# Power.net
KiCad netlist of a schematic drawn in Altium Designer
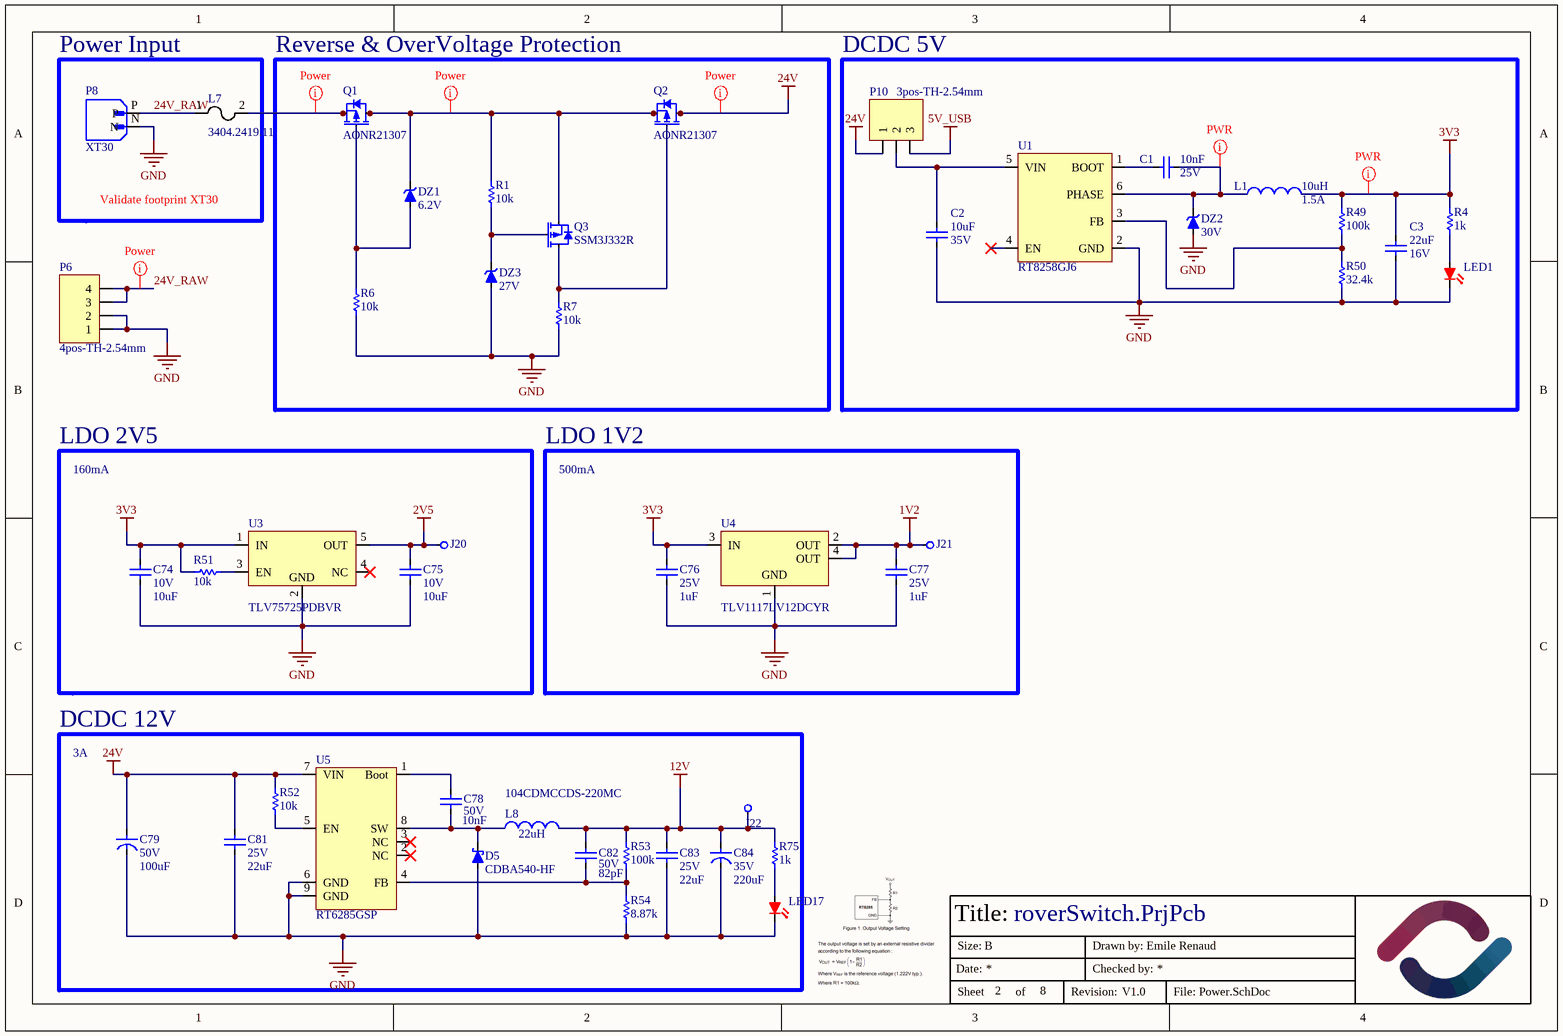
[diagram p0: Power.SchDoc]

(export (version "E")
  (design (tool "Eeschema 10.0.6"))
  (components
    (comp (ref "C1")
      (value "10nF")
      (footprint "CAPACITOR-0603")
      (description "10000 pF ±10% 25V Ceramic Capacitor X5R 0603 (1608 Metric)")
      (fields (field (name "VOLT") "25V") (field (name "Comment") "Capacitor-0603-10nF-25V-X5R"))
      (libsource (lib "Capacitors") (part "Capacitor-0603-10nF-25V-X5R"))
    )
    (comp (ref "C2")
      (value "10uF")
      (footprint "CAPACITOR-0805")
      (description "Capacitor-0805-10uF-35V-X5R")
      (fields (field (name "VOLT") "35V"))
      (libsource (lib "Capacitors") (part "Capacitor-0805-10uF-35V-X5R"))
    )
    (comp (ref "C3")
      (value "22uF")
      (footprint "CAPACITOR-0805")
      (description "Capacitor-0805-22uF-16V-X5R")
      (fields (field (name "VOLT") "16V"))
      (libsource (lib "Capacitors") (part "Capacitor-0805-22uF-16V-X5R"))
    )
    (comp (ref "C74")
      (value "10uF")
      (footprint "CAPACITOR-0603")
      (description "10 µF ±20% 10V Ceramic Capacitor X5R 0603 (1608 Metric)")
      (fields (field (name "VOLT") "10V") (field (name "Comment") "Capacitor-0603-10uF-10V-X5R"))
      (libsource (lib "Capacitors") (part "Capacitor-0603-10uF-10V-X5R"))
    )
    (comp (ref "C75")
      (value "10uF")
      (footprint "CAPACITOR-0603")
      (description "10 µF ±20% 10V Ceramic Capacitor X5R 0603 (1608 Metric)")
      (fields (field (name "VOLT") "10V") (field (name "Comment") "Capacitor-0603-10uF-10V-X5R"))
      (libsource (lib "Capacitors") (part "Capacitor-0603-10uF-10V-X5R"))
    )
    (comp (ref "C76")
      (value "1uF")
      (footprint "CAPACITOR-0603")
      (description "Capacitor-0603-1uF-25V-X5R")
      (fields (field (name "VOLT") "25V"))
      (libsource (lib "Capacitors") (part "Capacitor-0603-1uF-25V-X5R"))
    )
    (comp (ref "C77")
      (value "1uF")
      (footprint "CAPACITOR-0603")
      (description "Capacitor-0603-1uF-25V-X5R")
      (fields (field (name "VOLT") "25V"))
      (libsource (lib "Capacitors") (part "Capacitor-0603-1uF-25V-X5R"))
    )
    (comp (ref "C78")
      (value "10nF")
      (footprint "CAPACITOR-0603")
      (description "Capacitor-0603-10nF-50V-X7R")
      (fields (field (name "VOLT") "50V"))
      (libsource (lib "Capacitors") (part "Capacitor-0603-10nF-50V-X7R"))
    )
    (comp (ref "C79")
      (value "100uF")
      (footprint "CAP_J-V_8X10P5_RUB")
      (description "CAP ALUM 100UF 20% 50V SMD")
      (fields (field (name "VOLT") "50V") (field (name "Comment") "CAP ALUM 100UF 20% 25V SMD"))
      (libsource (lib "Capacitors-Electrolytic") (part "Capacitor-100uF-50V-SMD"))
    )
    (comp (ref "C81")
      (value "22uF")
      (footprint "CAPACITOR-0805")
      (description "Capacitor-0805-22uF-25V-X5R")
      (fields (field (name "VOLT") "25V"))
      (libsource (lib "Capacitors") (part "Capacitor-0805-22uF-25V-X5R"))
    )
    (comp (ref "C82")
      (value "82pF")
      (footprint "CAPACITOR-0603")
      (description "Capacitor-0603-82pF-50V-C0G")
      (fields (field (name "VOLT") "50V"))
      (libsource (lib "Capacitors") (part "Capacitor-0603-82pF-50V-C0G"))
    )
    (comp (ref "C83")
      (value "22uF")
      (footprint "CAPACITOR-0805")
      (description "Capacitor-0805-22uF-25V-X5R")
      (fields (field (name "VOLT") "25V"))
      (libsource (lib "Capacitors") (part "Capacitor-0805-22uF-25V-X5R"))
    )
    (comp (ref "C84")
      (value "220uF")
      (footprint "CAP_J-V_8X10P5_RUB")
      (description "CAP ALUM 220UF 20% 35V SMD")
      (fields (field (name "VOLT") "35V"))
      (libsource (lib "Capacitors-Electrolytic") (part "Capacitor-220uF-35V-SMD"))
    )
    (comp (ref "D5")
      (value "CDBA540-HF")
      (footprint "SMA/DO-214AC")
      (description "DIODE SCHOTTKY 40V 5A SMA")
      (libsource (lib "diodes") (part "CDBA540-HF"))
    )
    (comp (ref "DZ1")
      (value "BZT52C6V2-TP")
      (footprint "SOD-123")
      (description "Zener Diode 6.2 V 200 mW ±6% Surface Mount SOD-123")
      (fields (field (name "VOLT") "6.2V"))
      (libsource (lib "diodes-zener") (part "BZT52C6V2-TP"))
    )
    (comp (ref "DZ2")
      (value "MSS1P3L-M3/89A")
      (footprint "DO-219AD")
      (description "Diode 30 V 1A Surface Mount MicroSMP (DO-219AD)")
      (fields (field (name "VOLT") "30V"))
      (libsource (lib "diodes-zener") (part "MSS1P3L-M3/89A"))
    )
    (comp (ref "DZ3")
      (value "MMSZ5254B-TP")
      (footprint "SOD-123F")
      (description "DIODE ZENER 27V 500MW SOD123")
      (fields (field (name "VOLT") "27V"))
      (libsource (lib "diodes-zener") (part "MMSZ5254B-TP"))
    )
    (comp (ref "J20")
      (value "hole")
      (footprint "PCB_Footprints:PAD-0.53MM")
      (description "PAD for 28 AWG Solid Wire")
      (libsource (lib "JumpersAndHoles") (part "PAD 0.53mm AWG28-Solid"))
    )
    (comp (ref "J21")
      (value "hole")
      (footprint "PCB_Footprints:PAD-0.53MM")
      (description "PAD for 28 AWG Solid Wire")
      (libsource (lib "JumpersAndHoles") (part "PAD 0.53mm AWG28-Solid"))
    )
    (comp (ref "J22")
      (value "hole")
      (footprint "PCB_Footprints:PAD-0.53MM")
      (description "PAD for 28 AWG Solid Wire")
      (libsource (lib "JumpersAndHoles") (part "PAD 0.53mm AWG28-Solid"))
    )
    (comp (ref "L1")
      (value "10uH")
      (footprint "INDUCTOR_ASPI-4030S-100M")
      (description "10 µH Shielded Drum Core, Wirewound Inductor 1.5 A 100mOhm Nonstandard")
      (fields (field (name "CURRENT") "1.5A") (field (name "Comment") "ASPI-4030S-100M-T"))
      (libsource (lib "Inductors") (part "ASPI-4030S-100M-T"))
    )
    (comp (ref "L7")
      (value "3404.2419.11")
      (footprint "2-SMD-Fuse")
      (libsource (lib "Fuses") (part "3404.2419.11"))
    )
    (comp (ref "L8")
      (value "104CDMCCDS-220MC")
      (footprint "Inductor_22UH 5A")
      (description "FIXED IND 22UH 5A 66 MOHM SMD")
      (fields (field (name "ALTIUM_VALUE") "22uH"))
      (libsource (lib "Inductors") (part "104CDMCCDS-220MC"))
    )
    (comp (ref "LED1")
      (value "B1911USD-20D000114U1930")
      (footprint "LED-0603-2PIN")
      (description "LED RED CLEAR 1608 SMD")
      (libsource (lib "LEDs") (part "B1911USD-20D000114U1930"))
    )
    (comp (ref "LED17")
      (value "B1911USD-20D000114U1930")
      (footprint "LED-0603-2PIN")
      (description "LED RED CLEAR 1608 SMD")
      (libsource (lib "LEDs") (part "B1911USD-20D000114U1930"))
    )
    (comp (ref "P6")
      (value "4pos-TH-2.54mm")
      (footprint "HDR1X4")
      (description "4pos TH 2.54mm Header")
      (libsource (lib "Header") (part "4pos-TH-2.54mm"))
    )
    (comp (ref "P8")
      (value "XT30")
      (footprint "XT30PW_smd")
      (libsource (lib "BatteriesConnector") (part "XT30_pcb"))
    )
    (comp (ref "P10")
      (value "3pos-TH-2.54mm")
      (footprint "HDR1X3")
      (description "3pos TH 2.54mm Header")
      (libsource (lib "Header") (part "3pos-TH-2.54mm"))
    )
    (comp (ref "Q1")
      (value "AONR21307")
      (footprint "DFN8_3x3_Power")
      (description "MOSFET P-CH 30V 24A 8DFN")
      (libsource (lib "FET-P-Small") (part "AONR21307"))
    )
    (comp (ref "Q2")
      (value "AONR21307")
      (footprint "DFN8_3x3_Power")
      (description "MOSFET P-CH 30V 24A 8DFN")
      (libsource (lib "FET-P-Small") (part "AONR21307"))
    )
    (comp (ref "Q3")
      (value "SSM3J332R")
      (footprint "SOT-23-3")
      (description "P-Channel 30 V 6A (Ta) 1W (Ta) Surface Mount SOT-23F")
      (libsource (lib "FET-P-Small") (part "SSM3J332R"))
    )
    (comp (ref "R1")
      (value "10k")
      (footprint "Resistor-0603")
      (description "Resistor0603-10k")
      (fields (field (name "Comment") "SMT resistor"))
      (libsource (lib "Resistors") (part "Resistor0603-10k"))
    )
    (comp (ref "R4")
      (value "1k")
      (footprint "Resistor-0603")
      (description "Resistor0603-1k")
      (fields (field (name "Comment") "SMT resistor"))
      (libsource (lib "Resistors") (part "Resistor-0603-1k"))
    )
    (comp (ref "R6")
      (value "10k")
      (footprint "Resistor-0603")
      (description "Resistor0603-10k")
      (fields (field (name "Comment") "SMT resistor"))
      (libsource (lib "Resistors") (part "Resistor0603-10k"))
    )
    (comp (ref "R7")
      (value "10k")
      (footprint "Resistor-0603")
      (description "Resistor0603-10k")
      (fields (field (name "Comment") "SMT resistor"))
      (libsource (lib "Resistors") (part "Resistor0603-10k"))
    )
    (comp (ref "R49")
      (value "100k")
      (footprint "Resistor-0603")
      (description "Resistor0603-100k")
      (fields (field (name "Comment") "SMT resistor"))
      (libsource (lib "Resistors") (part "Resistor-0603-100k"))
    )
    (comp (ref "R50")
      (value "32.4k")
      (footprint "Resistor-0603")
      (description "Resistor0603-32.4k")
      (fields (field (name "Comment") "SMT resistor"))
      (libsource (lib "Resistors") (part "Resistor-0603-32.4k"))
    )
    (comp (ref "R51")
      (value "10k")
      (footprint "Resistor-0603")
      (description "Resistor0603-10k")
      (fields (field (name "Comment") "SMT resistor"))
      (libsource (lib "Resistors") (part "Resistor0603-10k"))
    )
    (comp (ref "R52")
      (value "10k")
      (footprint "Resistor-0603")
      (description "Resistor0603-10k")
      (fields (field (name "Comment") "SMT resistor"))
      (libsource (lib "Resistors") (part "Resistor-0603-10k"))
    )
    (comp (ref "R53")
      (value "100k")
      (footprint "Resistor-0603")
      (description "Resistor0603-100k")
      (fields (field (name "Comment") "SMT resistor"))
      (libsource (lib "Resistors") (part "Resistor-0603-100k"))
    )
    (comp (ref "R54")
      (value "8.87k")
      (footprint "Resistor-0603")
      (description "Resistor0603-8.87k")
      (fields (field (name "Comment") "SMT resistor"))
      (libsource (lib "Resistors") (part "Resistor-0603-8.87k"))
    )
    (comp (ref "R75")
      (value "1k")
      (footprint "Resistor-0603")
      (description "Resistor0603-1k")
      (fields (field (name "Comment") "SMT resistor"))
      (libsource (lib "Resistors") (part "Resistor-0603-1k"))
    )
    (comp (ref "U1")
      (value "RT8258GJ6")
      (footprint "SOT-23-6")
      (description "Switching Regulator/Controller")
      (fields (field (name "MANUFACTURER") "Richtek"))
      (libsource (lib "PowerKohrd") (part "REG_SWR_RT8258GJ6"))
    )
    (comp (ref "U3")
      (value "TLV75725PDBVR")
      (footprint "SOT-23-5")
      (description "IC REG 2.5V Positive Fixed 1 Output 1A SOT-23-5")
      (libsource (lib "PMIC-VoltageRegulators-LinearRegulators") (part "TLV75725PDBVR"))
    )
    (comp (ref "U4")
      (value "TLV1117LV12DCYR")
      (footprint "SOT-223-3/TO-261-3S")
      (description "IC REG 1.2V LINEAR 1A SOT223")
      (libsource (lib "PMIC-VoltageRegulators-LinearRegulators") (part "TLV1117LV12DCYR"))
    )
    (comp (ref "U5")
      (value "RT6285GSP")
      (footprint "SOIC-8-EXPOSED-PAD")
      (fields (field (name "HELPURL") "file:///C:/Users/Emile/Downloads/DS6285-00.pdf"))
      (libsource (lib "PMIC-VoltageRegulators-DCDCSwitchingRegulators") (part "RT6285GSP"))
    )
  )
  (nets
    (net (code "1") (name "/24V_RAW") (class "Default")
      (node (ref "L7") (pin "1") (pinfunction "1_1") (pintype "passive"))
      (node (ref "P6") (pin "3") (pinfunction "3_3") (pintype "passive"))
      (node (ref "P6") (pin "4") (pinfunction "4_4") (pintype "passive"))
      (node (ref "P8") (pin "P") (pinfunction "P_P") (pintype "power_in"))
    )
    (net (code "2") (name "1V2") (class "Default")
      (node (ref "C77") (pin "2") (pinfunction "2_2") (pintype "passive"))
      (node (ref "J21") (pin "1") (pinfunction "1_1") (pintype "passive"))
      (node (ref "U4") (pin "2") (pinfunction "OUT_2") (pintype "passive"))
      (node (ref "U4") (pin "4") (pinfunction "OUT_4") (pintype "passive"))
    )
    (net (code "3") (name "2V5") (class "Default")
      (node (ref "C75") (pin "1") (pinfunction "1_1") (pintype "passive"))
      (node (ref "J20") (pin "1") (pinfunction "1_1") (pintype "passive"))
      (node (ref "U3") (pin "5") (pinfunction "OUT_5") (pintype "passive"))
    )
    (net (code "4") (name "3V3") (class "Default")
      (node (ref "C3") (pin "2") (pinfunction "2_2") (pintype "passive"))
      (node (ref "C74") (pin "1") (pinfunction "1_1") (pintype "passive"))
      (node (ref "C76") (pin "2") (pinfunction "2_2") (pintype "passive"))
      (node (ref "L1") (pin "2") (pinfunction "2_2") (pintype "passive"))
      (node (ref "R4") (pin "2") (pinfunction "2_2") (pintype "passive"))
      (node (ref "R49") (pin "2") (pinfunction "2_2") (pintype "passive"))
      (node (ref "R51") (pin "2") (pinfunction "2_2") (pintype "passive"))
      (node (ref "U3") (pin "1") (pinfunction "IN_1") (pintype "passive"))
      (node (ref "U4") (pin "3") (pinfunction "IN_3") (pintype "passive"))
    )
    (net (code "5") (name "5V_USB") (class "Default")
      (node (ref "P10") (pin "3") (pinfunction "3_3") (pintype "passive"))
    )
    (net (code "6") (name "12V") (class "Default")
      (node (ref "C82") (pin "2") (pinfunction "2_2") (pintype "passive"))
      (node (ref "C83") (pin "2") (pinfunction "2_2") (pintype "passive"))
      (node (ref "C84") (pin "1") (pinfunction "1_1") (pintype "passive"))
      (node (ref "J22") (pin "1") (pinfunction "1_1") (pintype "passive"))
      (node (ref "L8") (pin "2") (pinfunction "2_2") (pintype "passive"))
      (node (ref "R53") (pin "2") (pinfunction "2_2") (pintype "passive"))
      (node (ref "R75") (pin "2") (pinfunction "2_2") (pintype "passive"))
    )
    (net (code "7") (name "24V") (class "Default")
      (node (ref "C79") (pin "1") (pinfunction "1_1") (pintype "passive"))
      (node (ref "C81") (pin "2") (pinfunction "2_2") (pintype "passive"))
      (node (ref "P10") (pin "1") (pinfunction "1_1") (pintype "passive"))
      (node (ref "Q2") (pin "5") (pinfunction "D_5") (pintype "passive"))
      (node (ref "Q2") (pin "6") (pinfunction "D_6") (pintype "passive"))
      (node (ref "Q2") (pin "7") (pinfunction "D_7") (pintype "passive"))
      (node (ref "Q2") (pin "8") (pinfunction "D_8") (pintype "passive"))
      (node (ref "R52") (pin "2") (pinfunction "2_2") (pintype "passive"))
      (node (ref "U5") (pin "7") (pinfunction "VIN_7") (pintype "passive"))
    )
    (net (code "8") (name "GND") (class "Default")
      (node (ref "C2") (pin "1") (pinfunction "1_1") (pintype "passive"))
      (node (ref "C3") (pin "1") (pinfunction "1_1") (pintype "passive"))
      (node (ref "C74") (pin "2") (pinfunction "2_2") (pintype "passive"))
      (node (ref "C75") (pin "2") (pinfunction "2_2") (pintype "passive"))
      (node (ref "C76") (pin "1") (pinfunction "1_1") (pintype "passive"))
      (node (ref "C77") (pin "1") (pinfunction "1_1") (pintype "passive"))
      (node (ref "C79") (pin "2") (pinfunction "2_2") (pintype "passive"))
      (node (ref "C81") (pin "1") (pinfunction "1_1") (pintype "passive"))
      (node (ref "C83") (pin "1") (pinfunction "1_1") (pintype "passive"))
      (node (ref "C84") (pin "2") (pinfunction "2_2") (pintype "passive"))
      (node (ref "D5") (pin "1") (pinfunction "A_1") (pintype "passive"))
      (node (ref "DZ2") (pin "2") (pinfunction "A_2") (pintype "passive"))
      (node (ref "DZ3") (pin "1") (pinfunction "A_1") (pintype "passive"))
      (node (ref "LED1") (pin "1") (pinfunction "K_1") (pintype "passive"))
      (node (ref "LED17") (pin "1") (pinfunction "K_1") (pintype "passive"))
      (node (ref "P6") (pin "1") (pinfunction "1_1") (pintype "passive"))
      (node (ref "P6") (pin "2") (pinfunction "2_2") (pintype "passive"))
      (node (ref "P8") (pin "N") (pinfunction "N_N") (pintype "power_in"))
      (node (ref "R50") (pin "1") (pinfunction "1_1") (pintype "passive"))
      (node (ref "R54") (pin "1") (pinfunction "1_1") (pintype "passive"))
      (node (ref "R6") (pin "1") (pinfunction "1_1") (pintype "passive"))
      (node (ref "R7") (pin "1") (pinfunction "1_1") (pintype "passive"))
      (node (ref "U1") (pin "2") (pinfunction "GND_2") (pintype "passive"))
      (node (ref "U3") (pin "2") (pinfunction "GND_2") (pintype "passive"))
      (node (ref "U4") (pin "1") (pinfunction "GND_1") (pintype "passive"))
      (node (ref "U5") (pin "6") (pinfunction "GND_6") (pintype "passive"))
      (node (ref "U5") (pin "9") (pinfunction "GND_9") (pintype "passive"))
    )
    (net (code "9") (name "Net-(D5-K)") (class "Default")
      (node (ref "C78") (pin "1") (pinfunction "1_1") (pintype "passive"))
      (node (ref "D5") (pin "2") (pinfunction "K_2") (pintype "passive"))
      (node (ref "L8") (pin "1") (pinfunction "1_1") (pintype "passive"))
      (node (ref "U5") (pin "8") (pinfunction "SW_8") (pintype "passive"))
    )
    (net (code "10") (name "Net-(DZ1-A)") (class "Default")
      (node (ref "DZ1") (pin "1") (pinfunction "A_1") (pintype "passive"))
      (node (ref "Q1") (pin "4") (pinfunction "G_4") (pintype "passive"))
      (node (ref "R6") (pin "2") (pinfunction "2_2") (pintype "passive"))
    )
    (net (code "11") (name "Net-(DZ1-K)") (class "Default")
      (node (ref "DZ1") (pin "2") (pinfunction "K_2") (pintype "passive"))
      (node (ref "Q1") (pin "5") (pinfunction "D_5") (pintype "passive"))
      (node (ref "Q1") (pin "6") (pinfunction "D_6") (pintype "passive"))
      (node (ref "Q1") (pin "7") (pinfunction "D_7") (pintype "passive"))
      (node (ref "Q1") (pin "8") (pinfunction "D_8") (pintype "passive"))
      (node (ref "Q2") (pin "1") (pinfunction "S_1") (pintype "passive"))
      (node (ref "Q2") (pin "2") (pinfunction "S_2") (pintype "passive"))
      (node (ref "Q2") (pin "3") (pinfunction "S_3") (pintype "passive"))
      (node (ref "Q3") (pin "2") (pinfunction "S_2") (pintype "passive"))
      (node (ref "R1") (pin "2") (pinfunction "2_2") (pintype "passive"))
    )
    (net (code "12") (name "Net-(DZ2-K)") (class "Default")
      (node (ref "C1") (pin "2") (pinfunction "2_2") (pintype "passive"))
      (node (ref "DZ2") (pin "1") (pinfunction "K_1") (pintype "passive"))
      (node (ref "L1") (pin "1") (pinfunction "1_1") (pintype "passive"))
      (node (ref "U1") (pin "6") (pinfunction "PHASE_6") (pintype "passive"))
    )
    (net (code "13") (name "Net-(DZ3-K)") (class "Default")
      (node (ref "DZ3") (pin "2") (pinfunction "K_2") (pintype "passive"))
      (node (ref "Q3") (pin "1") (pinfunction "G_1") (pintype "passive"))
      (node (ref "R1") (pin "1") (pinfunction "1_1") (pintype "passive"))
    )
    (net (code "14") (name "Net-(L7-Pad2)") (class "Default")
      (node (ref "L7") (pin "2") (pinfunction "2_2") (pintype "passive"))
      (node (ref "Q1") (pin "1") (pinfunction "S_1") (pintype "passive"))
      (node (ref "Q1") (pin "2") (pinfunction "S_2") (pintype "passive"))
      (node (ref "Q1") (pin "3") (pinfunction "S_3") (pintype "passive"))
    )
    (net (code "15") (name "Net-(LED1-R)") (class "Default")
      (node (ref "LED1") (pin "2") (pinfunction "R_2") (pintype "passive"))
      (node (ref "R4") (pin "1") (pinfunction "1_1") (pintype "passive"))
    )
    (net (code "16") (name "Net-(LED17-R)") (class "Default")
      (node (ref "LED17") (pin "2") (pinfunction "R_2") (pintype "passive"))
      (node (ref "R75") (pin "1") (pinfunction "1_1") (pintype "passive"))
    )
    (net (code "17") (name "Net-(Q2-G)") (class "Default")
      (node (ref "Q2") (pin "4") (pinfunction "G_4") (pintype "passive"))
      (node (ref "Q3") (pin "3") (pinfunction "D_3") (pintype "passive"))
      (node (ref "R7") (pin "2") (pinfunction "2_2") (pintype "passive"))
    )
    (net (code "18") (name "Net-(U1-BOOT)") (class "Default")
      (node (ref "C1") (pin "1") (pinfunction "1_1") (pintype "passive"))
      (node (ref "U1") (pin "1") (pinfunction "BOOT_1") (pintype "passive"))
    )
    (net (code "19") (name "Net-(U1-FB)") (class "Default")
      (node (ref "R49") (pin "1") (pinfunction "1_1") (pintype "passive"))
      (node (ref "R50") (pin "2") (pinfunction "2_2") (pintype "passive"))
      (node (ref "U1") (pin "3") (pinfunction "FB_3") (pintype "passive"))
    )
    (net (code "20") (name "Net-(U1-VIN)") (class "Default")
      (node (ref "C2") (pin "2") (pinfunction "2_2") (pintype "passive"))
      (node (ref "P10") (pin "2") (pinfunction "2_2") (pintype "passive"))
      (node (ref "U1") (pin "5") (pinfunction "VIN_5") (pintype "passive"))
    )
    (net (code "21") (name "Net-(U3-EN)") (class "Default")
      (node (ref "R51") (pin "1") (pinfunction "1_1") (pintype "passive"))
      (node (ref "U3") (pin "3") (pinfunction "EN_3") (pintype "passive"))
    )
    (net (code "22") (name "Net-(U5-Boot)") (class "Default")
      (node (ref "C78") (pin "2") (pinfunction "2_2") (pintype "passive"))
      (node (ref "U5") (pin "1") (pinfunction "Boot_1") (pintype "passive"))
    )
    (net (code "23") (name "Net-(U5-EN)") (class "Default")
      (node (ref "R52") (pin "1") (pinfunction "1_1") (pintype "passive"))
      (node (ref "U5") (pin "5") (pinfunction "EN_5") (pintype "passive"))
    )
    (net (code "24") (name "Net-(U5-FB)") (class "Default")
      (node (ref "C82") (pin "1") (pinfunction "1_1") (pintype "passive"))
      (node (ref "R53") (pin "1") (pinfunction "1_1") (pintype "passive"))
      (node (ref "R54") (pin "2") (pinfunction "2_2") (pintype "passive"))
      (node (ref "U5") (pin "4") (pinfunction "FB_4") (pintype "passive"))
    )
    (net (code "25") (name "unconnected-(U1-EN-Pad4)") (class "Default")
      (node (ref "U1") (pin "4") (pinfunction "EN_4") (pintype "passive+no_connect"))
    )
    (net (code "26") (name "unconnected-(U3-NC-Pad4)") (class "Default")
      (node (ref "U3") (pin "4") (pinfunction "NC_4") (pintype "passive+no_connect"))
    )
    (net (code "27") (name "unconnected-(U5-NC-Pad2)") (class "Default")
      (node (ref "U5") (pin "2") (pinfunction "NC_2") (pintype "passive+no_connect"))
    )
    (net (code "28") (name "unconnected-(U5-NC-Pad3)") (class "Default")
      (node (ref "U5") (pin "3") (pinfunction "NC_3") (pintype "passive+no_connect"))
    )
  )
)
